# health_monitor.net
KiCad netlist of a schematic drawn in EAGLE
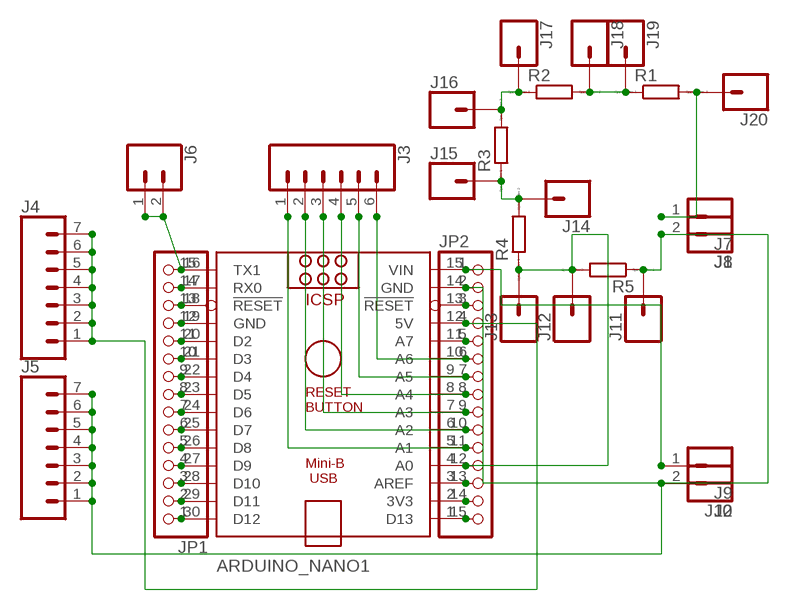
[diagram p0: schematic, sheet 1]

(export (version "E")
  (design (tool "Eeschema 10.0.6"))
  (components
    (comp (ref "ARDUINO_NANO1")
      (value "ARDUINO_NANO")
      (footprint "eagle-import:ARDUINO_NANO")
      (libsource (lib "eagle-import") (part "ARDUINO_NANO"))
    )
    (comp (ref "J1")
      (value "CONN_025MM")
      (footprint "eagle-import:SCREWTERMINAL-5MM-2")
      (libsource (lib "eagle-import") (part "CONN_025MM"))
    )
    (comp (ref "J2")
      (value "CONN_025MM")
      (footprint "eagle-import:SCREWTERMINAL-5MM-2")
      (libsource (lib "eagle-import") (part "CONN_025MM"))
    )
    (comp (ref "J3")
      (value "CONN_06LONGPADS")
      (footprint "eagle-import:1X06_LONGPADS")
      (libsource (lib "eagle-import") (part "CONN_06LONGPADS"))
    )
    (comp (ref "J4")
      (value "CONN_07LONGPADS")
      (footprint "eagle-import:1X07_LONGPADS")
      (libsource (lib "eagle-import") (part "CONN_07LONGPADS"))
    )
    (comp (ref "J5")
      (value "CONN_07LONGPADS")
      (footprint "eagle-import:1X07_LONGPADS")
      (libsource (lib "eagle-import") (part "CONN_07LONGPADS"))
    )
    (comp (ref "J6")
      (value "CONN_02PTH3")
      (footprint "eagle-import:1X02_LONGPADS")
      (libsource (lib "eagle-import") (part "CONN_02PTH3"))
    )
    (comp (ref "J7")
      (value "CONN_01PTH_LONGPAD")
      (footprint "eagle-import:1X01_LONGPAD")
      (libsource (lib "eagle-import") (part "CONN_01PTH_LONGPAD"))
    )
    (comp (ref "J8")
      (value "CONN_01PTH_LONGPAD")
      (footprint "eagle-import:1X01_LONGPAD")
      (libsource (lib "eagle-import") (part "CONN_01PTH_LONGPAD"))
    )
    (comp (ref "J9")
      (value "CONN_01PTH_LONGPAD")
      (footprint "eagle-import:1X01_LONGPAD")
      (libsource (lib "eagle-import") (part "CONN_01PTH_LONGPAD"))
    )
    (comp (ref "J10")
      (value "CONN_01PTH_LONGPAD")
      (footprint "eagle-import:1X01_LONGPAD")
      (libsource (lib "eagle-import") (part "CONN_01PTH_LONGPAD"))
    )
    (comp (ref "J11")
      (value "CONN_01PTH_LONGPAD")
      (footprint "eagle-import:1X01_LONGPAD")
      (libsource (lib "eagle-import") (part "CONN_01PTH_LONGPAD"))
    )
    (comp (ref "J12")
      (value "CONN_01PTH_LONGPAD")
      (footprint "eagle-import:1X01_LONGPAD")
      (libsource (lib "eagle-import") (part "CONN_01PTH_LONGPAD"))
    )
    (comp (ref "J13")
      (value "CONN_01PTH_LONGPAD")
      (footprint "eagle-import:1X01_LONGPAD")
      (libsource (lib "eagle-import") (part "CONN_01PTH_LONGPAD"))
    )
    (comp (ref "J14")
      (value "CONN_01PTH_LONGPAD")
      (footprint "eagle-import:1X01_LONGPAD")
      (libsource (lib "eagle-import") (part "CONN_01PTH_LONGPAD"))
    )
    (comp (ref "J15")
      (value "CONN_01PTH_LONGPAD")
      (footprint "eagle-import:1X01_LONGPAD")
      (libsource (lib "eagle-import") (part "CONN_01PTH_LONGPAD"))
    )
    (comp (ref "J16")
      (value "CONN_01PTH_LONGPAD")
      (footprint "eagle-import:1X01_LONGPAD")
      (libsource (lib "eagle-import") (part "CONN_01PTH_LONGPAD"))
    )
    (comp (ref "J17")
      (value "CONN_01PTH_LONGPAD")
      (footprint "eagle-import:1X01_LONGPAD")
      (libsource (lib "eagle-import") (part "CONN_01PTH_LONGPAD"))
    )
    (comp (ref "J18")
      (value "CONN_01PTH_LONGPAD")
      (footprint "eagle-import:1X01_LONGPAD")
      (libsource (lib "eagle-import") (part "CONN_01PTH_LONGPAD"))
    )
    (comp (ref "J19")
      (value "CONN_01PTH_LONGPAD")
      (footprint "eagle-import:1X01_LONGPAD")
      (libsource (lib "eagle-import") (part "CONN_01PTH_LONGPAD"))
    )
    (comp (ref "J20")
      (value "CONN_01PTH_LONGPAD")
      (footprint "eagle-import:1X01_LONGPAD")
      (libsource (lib "eagle-import") (part "CONN_01PTH_LONGPAD"))
    )
    (comp (ref "JP1")
      (value "PINHD-1X15")
      (footprint "eagle-import:1X15")
      (libsource (lib "eagle-import") (part "PINHD-1X15"))
    )
    (comp (ref "JP2")
      (value "PINHD-1X15")
      (footprint "eagle-import:1X15")
      (libsource (lib "eagle-import") (part "PINHD-1X15"))
    )
    (comp (ref "R1")
      (value "R0204/7")
      (footprint "eagle-import:0204_7")
      (libsource (lib "eagle-import") (part "R0204/7"))
    )
    (comp (ref "R2")
      (value "R0204/7")
      (footprint "eagle-import:0204_7")
      (libsource (lib "eagle-import") (part "R0204/7"))
    )
    (comp (ref "R3")
      (value "R0204/7")
      (footprint "eagle-import:0204_7")
      (libsource (lib "eagle-import") (part "R0204/7"))
    )
    (comp (ref "R4")
      (value "R0204/7")
      (footprint "eagle-import:0204_7")
      (libsource (lib "eagle-import") (part "R0204/7"))
    )
    (comp (ref "R5")
      (value "R0204/7")
      (footprint "eagle-import:0204_7")
      (libsource (lib "eagle-import") (part "R0204/7"))
    )
  )
  (nets
    (net (code "1") (name "Net-(ARDUINO_NANO1-3V3)") (class "Default")
      (node (ref "ARDUINO_NANO1") (pin "2") (pinfunction "3V3_2") (pintype "output"))
      (node (ref "JP2") (pin "14") (pinfunction "14_14") (pintype "passive"))
    )
    (net (code "2") (name "Net-(ARDUINO_NANO1-5V)") (class "Default")
      (node (ref "ARDUINO_NANO1") (pin "12") (pinfunction "5V_12") (pintype "power_in"))
      (node (ref "J4") (pin "1") (pinfunction "1_1") (pintype "passive"))
      (node (ref "J4") (pin "2") (pinfunction "2_2") (pintype "passive"))
      (node (ref "J4") (pin "3") (pinfunction "3_3") (pintype "passive"))
      (node (ref "J4") (pin "4") (pinfunction "4_4") (pintype "passive"))
      (node (ref "J4") (pin "5") (pinfunction "5_5") (pintype "passive"))
      (node (ref "J4") (pin "6") (pinfunction "6_6") (pintype "passive"))
      (node (ref "J4") (pin "7") (pinfunction "7_7") (pintype "passive"))
      (node (ref "JP2") (pin "4") (pinfunction "4_4") (pintype "passive"))
    )
    (net (code "3") (name "Net-(ARDUINO_NANO1-A0)") (class "Default")
      (node (ref "ARDUINO_NANO1") (pin "4") (pinfunction "A0_4") (pintype "bidirectional"))
      (node (ref "J12") (pin "1") (pinfunction "1_1") (pintype "passive"))
      (node (ref "J13") (pin "1") (pinfunction "1_1") (pintype "passive"))
      (node (ref "JP2") (pin "12") (pinfunction "12_12") (pintype "passive"))
      (node (ref "R4") (pin "1") (pinfunction "1_1") (pintype "passive"))
      (node (ref "R5") (pin "2") (pinfunction "2_2") (pintype "passive"))
    )
    (net (code "4") (name "Net-(ARDUINO_NANO1-A1)") (class "Default")
      (node (ref "ARDUINO_NANO1") (pin "5") (pinfunction "A1_5") (pintype "bidirectional"))
      (node (ref "J3") (pin "1") (pinfunction "1_1") (pintype "passive"))
      (node (ref "JP2") (pin "11") (pinfunction "11_11") (pintype "passive"))
    )
    (net (code "5") (name "Net-(ARDUINO_NANO1-A2)") (class "Default")
      (node (ref "ARDUINO_NANO1") (pin "6") (pinfunction "A2_6") (pintype "bidirectional"))
      (node (ref "J3") (pin "2") (pinfunction "2_2") (pintype "passive"))
      (node (ref "JP2") (pin "10") (pinfunction "10_10") (pintype "passive"))
    )
    (net (code "6") (name "Net-(ARDUINO_NANO1-A3)") (class "Default")
      (node (ref "ARDUINO_NANO1") (pin "7") (pinfunction "A3_7") (pintype "bidirectional"))
      (node (ref "J3") (pin "3") (pinfunction "3_3") (pintype "passive"))
      (node (ref "JP2") (pin "9") (pinfunction "9_9") (pintype "passive"))
    )
    (net (code "7") (name "Net-(ARDUINO_NANO1-A4)") (class "Default")
      (node (ref "ARDUINO_NANO1") (pin "8") (pinfunction "A4_8") (pintype "bidirectional"))
      (node (ref "J3") (pin "4") (pinfunction "4_4") (pintype "passive"))
      (node (ref "JP2") (pin "8") (pinfunction "8_8") (pintype "passive"))
    )
    (net (code "8") (name "Net-(ARDUINO_NANO1-A5)") (class "Default")
      (node (ref "ARDUINO_NANO1") (pin "9") (pinfunction "A5_9") (pintype "bidirectional"))
      (node (ref "J3") (pin "5") (pinfunction "5_5") (pintype "passive"))
      (node (ref "JP2") (pin "7") (pinfunction "7_7") (pintype "passive"))
    )
    (net (code "9") (name "Net-(ARDUINO_NANO1-A6)") (class "Default")
      (node (ref "ARDUINO_NANO1") (pin "10") (pinfunction "A6_10") (pintype "bidirectional"))
      (node (ref "J3") (pin "6") (pinfunction "6_6") (pintype "passive"))
      (node (ref "JP2") (pin "6") (pinfunction "6_6") (pintype "passive"))
    )
    (net (code "10") (name "Net-(ARDUINO_NANO1-A7)") (class "Default")
      (node (ref "ARDUINO_NANO1") (pin "11") (pinfunction "A7_11") (pintype "bidirectional"))
      (node (ref "JP2") (pin "5") (pinfunction "5_5") (pintype "passive"))
    )
    (net (code "11") (name "Net-(ARDUINO_NANO1-AREF)") (class "Default")
      (node (ref "ARDUINO_NANO1") (pin "3") (pinfunction "AREF_3") (pintype "input"))
      (node (ref "JP2") (pin "13") (pinfunction "13_13") (pintype "passive"))
    )
    (net (code "12") (name "Net-(ARDUINO_NANO1-D2)") (class "Default")
      (node (ref "ARDUINO_NANO1") (pin "20") (pinfunction "D2_20") (pintype "bidirectional"))
      (node (ref "JP1") (pin "11") (pinfunction "11_11") (pintype "passive"))
    )
    (net (code "13") (name "Net-(ARDUINO_NANO1-D3)") (class "Default")
      (node (ref "ARDUINO_NANO1") (pin "21") (pinfunction "D3_21") (pintype "bidirectional"))
      (node (ref "JP1") (pin "10") (pinfunction "10_10") (pintype "passive"))
    )
    (net (code "14") (name "Net-(ARDUINO_NANO1-D4)") (class "Default")
      (node (ref "ARDUINO_NANO1") (pin "22") (pinfunction "D4_22") (pintype "bidirectional"))
      (node (ref "JP1") (pin "9") (pinfunction "9_9") (pintype "passive"))
    )
    (net (code "15") (name "Net-(ARDUINO_NANO1-D5)") (class "Default")
      (node (ref "ARDUINO_NANO1") (pin "23") (pinfunction "D5_23") (pintype "bidirectional"))
      (node (ref "JP1") (pin "8") (pinfunction "8_8") (pintype "passive"))
    )
    (net (code "16") (name "Net-(ARDUINO_NANO1-D6)") (class "Default")
      (node (ref "ARDUINO_NANO1") (pin "24") (pinfunction "D6_24") (pintype "bidirectional"))
      (node (ref "JP1") (pin "7") (pinfunction "7_7") (pintype "passive"))
    )
    (net (code "17") (name "Net-(ARDUINO_NANO1-D7)") (class "Default")
      (node (ref "ARDUINO_NANO1") (pin "25") (pinfunction "D7_25") (pintype "bidirectional"))
      (node (ref "JP1") (pin "6") (pinfunction "6_6") (pintype "passive"))
    )
    (net (code "18") (name "Net-(ARDUINO_NANO1-D8)") (class "Default")
      (node (ref "ARDUINO_NANO1") (pin "26") (pinfunction "D8_26") (pintype "bidirectional"))
      (node (ref "JP1") (pin "5") (pinfunction "5_5") (pintype "passive"))
    )
    (net (code "19") (name "Net-(ARDUINO_NANO1-D9)") (class "Default")
      (node (ref "ARDUINO_NANO1") (pin "27") (pinfunction "D9_27") (pintype "bidirectional"))
      (node (ref "JP1") (pin "4") (pinfunction "4_4") (pintype "passive"))
    )
    (net (code "20") (name "Net-(ARDUINO_NANO1-D10)") (class "Default")
      (node (ref "ARDUINO_NANO1") (pin "28") (pinfunction "D10_28") (pintype "bidirectional"))
      (node (ref "JP1") (pin "3") (pinfunction "3_3") (pintype "passive"))
    )
    (net (code "21") (name "Net-(ARDUINO_NANO1-D11)") (class "Default")
      (node (ref "ARDUINO_NANO1") (pin "29") (pinfunction "D11_29") (pintype "bidirectional"))
      (node (ref "JP1") (pin "2") (pinfunction "2_2") (pintype "passive"))
    )
    (net (code "22") (name "Net-(ARDUINO_NANO1-D12)") (class "Default")
      (node (ref "ARDUINO_NANO1") (pin "30") (pinfunction "D12_30") (pintype "bidirectional"))
      (node (ref "JP1") (pin "1") (pinfunction "1_1") (pintype "passive"))
    )
    (net (code "23") (name "Net-(ARDUINO_NANO1-D13)") (class "Default")
      (node (ref "ARDUINO_NANO1") (pin "1") (pinfunction "D13_1") (pintype "bidirectional"))
      (node (ref "JP2") (pin "15") (pinfunction "15_15") (pintype "passive"))
    )
    (net (code "24") (name "Net-(ARDUINO_NANO1-GND-Pad14)") (class "Default")
      (node (ref "ARDUINO_NANO1") (pin "14") (pinfunction "GND_14") (pintype "power_in"))
      (node (ref "J1") (pin "2") (pinfunction "2_2") (pintype "passive"))
      (node (ref "J10") (pin "1") (pinfunction "1_1") (pintype "passive"))
      (node (ref "J11") (pin "1") (pinfunction "1_1") (pintype "passive"))
      (node (ref "J2") (pin "2") (pinfunction "2_2") (pintype "passive"))
      (node (ref "J5") (pin "1") (pinfunction "1_1") (pintype "passive"))
      (node (ref "J5") (pin "2") (pinfunction "2_2") (pintype "passive"))
      (node (ref "J5") (pin "3") (pinfunction "3_3") (pintype "passive"))
      (node (ref "J5") (pin "4") (pinfunction "4_4") (pintype "passive"))
      (node (ref "J5") (pin "5") (pinfunction "5_5") (pintype "passive"))
      (node (ref "J5") (pin "6") (pinfunction "6_6") (pintype "passive"))
      (node (ref "J5") (pin "7") (pinfunction "7_7") (pintype "passive"))
      (node (ref "J8") (pin "1") (pinfunction "1_1") (pintype "passive"))
      (node (ref "JP2") (pin "2") (pinfunction "2_2") (pintype "passive"))
      (node (ref "R5") (pin "1") (pinfunction "1_1") (pintype "passive"))
    )
    (net (code "25") (name "Net-(ARDUINO_NANO1-GND-Pad19)") (class "Default")
      (node (ref "ARDUINO_NANO1") (pin "19") (pinfunction "GND_19") (pintype "power_in"))
      (node (ref "JP1") (pin "12") (pinfunction "12_12") (pintype "passive"))
    )
    (net (code "26") (name "Net-(ARDUINO_NANO1-RX0)") (class "Default")
      (node (ref "ARDUINO_NANO1") (pin "17") (pinfunction "RX0_17") (pintype "bidirectional"))
      (node (ref "JP1") (pin "14") (pinfunction "14_14") (pintype "passive"))
    )
    (net (code "27") (name "Net-(ARDUINO_NANO1-TX1)") (class "Default")
      (node (ref "ARDUINO_NANO1") (pin "16") (pinfunction "TX1_16") (pintype "bidirectional"))
      (node (ref "J6") (pin "1") (pinfunction "1_1") (pintype "passive"))
      (node (ref "J6") (pin "2") (pinfunction "2_2") (pintype "passive"))
      (node (ref "JP1") (pin "15") (pinfunction "15_15") (pintype "passive"))
    )
    (net (code "28") (name "Net-(ARDUINO_NANO1-VIN)") (class "Default")
      (node (ref "ARDUINO_NANO1") (pin "15") (pinfunction "VIN_15") (pintype "power_in"))
      (node (ref "J2") (pin "1") (pinfunction "1_1") (pintype "passive"))
      (node (ref "J9") (pin "1") (pinfunction "1_1") (pintype "passive"))
      (node (ref "JP2") (pin "1") (pinfunction "1_1") (pintype "passive"))
    )
    (net (code "29") (name "Net-(ARDUINO_NANO1-~{RESET}-Pad13)") (class "Default")
      (node (ref "ARDUINO_NANO1") (pin "13") (pinfunction "~{RESET}_13") (pintype "input"))
      (node (ref "JP2") (pin "3") (pinfunction "3_3") (pintype "passive"))
    )
    (net (code "30") (name "Net-(ARDUINO_NANO1-~{RESET}-Pad18)") (class "Default")
      (node (ref "ARDUINO_NANO1") (pin "18") (pinfunction "~{RESET}_18") (pintype "input"))
      (node (ref "JP1") (pin "13") (pinfunction "13_13") (pintype "passive"))
    )
    (net (code "31") (name "Net-(J1-Pad1)") (class "Default")
      (node (ref "J1") (pin "1") (pinfunction "1_1") (pintype "passive"))
      (node (ref "J20") (pin "1") (pinfunction "1_1") (pintype "passive"))
      (node (ref "J7") (pin "1") (pinfunction "1_1") (pintype "passive"))
      (node (ref "R1") (pin "2") (pinfunction "2_2") (pintype "passive"))
    )
    (net (code "32") (name "Net-(J14-Pad1)") (class "Default")
      (node (ref "J14") (pin "1") (pinfunction "1_1") (pintype "passive"))
      (node (ref "J15") (pin "1") (pinfunction "1_1") (pintype "passive"))
      (node (ref "R3") (pin "1") (pinfunction "1_1") (pintype "passive"))
      (node (ref "R4") (pin "2") (pinfunction "2_2") (pintype "passive"))
    )
    (net (code "33") (name "Net-(J16-Pad1)") (class "Default")
      (node (ref "J16") (pin "1") (pinfunction "1_1") (pintype "passive"))
      (node (ref "J17") (pin "1") (pinfunction "1_1") (pintype "passive"))
      (node (ref "R2") (pin "1") (pinfunction "1_1") (pintype "passive"))
      (node (ref "R3") (pin "2") (pinfunction "2_2") (pintype "passive"))
    )
    (net (code "34") (name "Net-(J18-Pad1)") (class "Default")
      (node (ref "J18") (pin "1") (pinfunction "1_1") (pintype "passive"))
      (node (ref "J19") (pin "1") (pinfunction "1_1") (pintype "passive"))
      (node (ref "R1") (pin "1") (pinfunction "1_1") (pintype "passive"))
      (node (ref "R2") (pin "2") (pinfunction "2_2") (pintype "passive"))
    )
  )
)
